# Type_Specific.net
KiCad netlist of a schematic drawn in Altium Designer
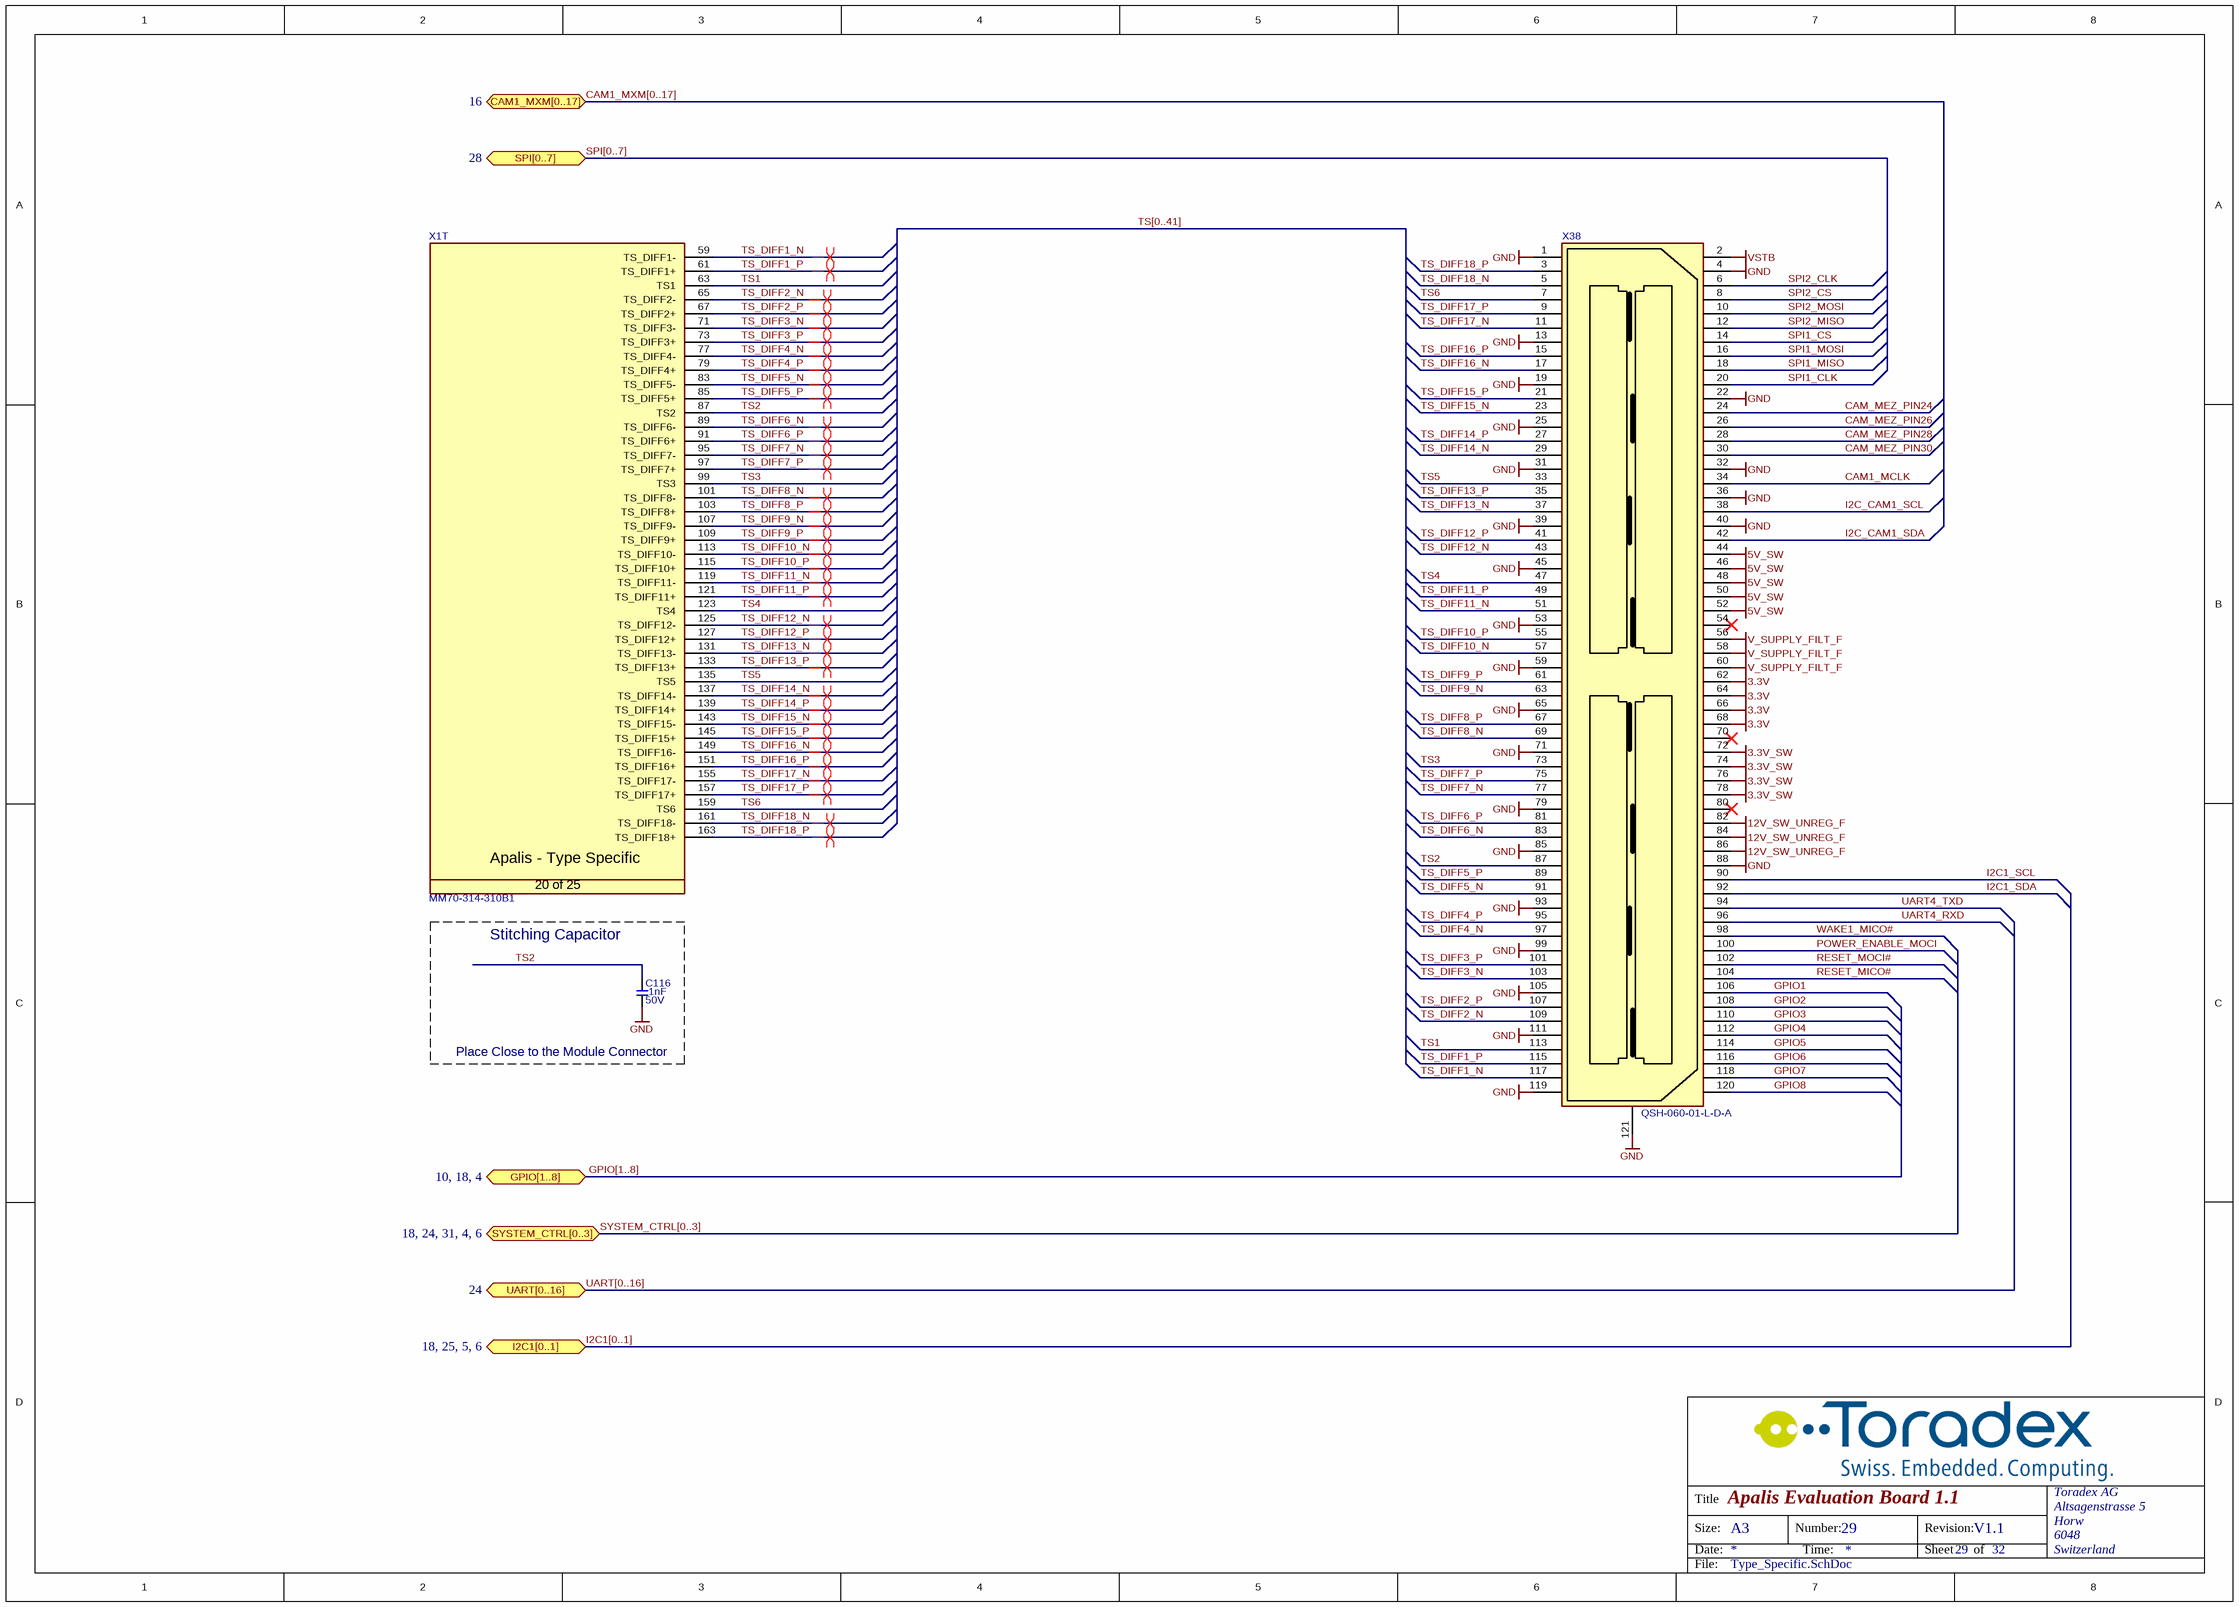
[diagram p0: Type_Specific.SchDoc]

(export (version "E")
  (design (tool "Eeschema 10.0.6"))
  (components
    (comp (ref "C116")
      (value "1nF")
      (footprint "CAPC1005X60N")
      (description "Capacitor Ceramic X7R 1nF 50V 10% 0402")
      (fields (field (name "TOLERANCE") "10%") (field (name "RATING") "50V"))
      (libsource (lib "Apalis Evaluation Board") (part "C-X7R-1nF-50V-10%-0402"))
    )
    (comp (ref "X1")
      (value "CON-JAE-MM70-314-310B1-314-0.5mm")
      (footprint "T_JAE_MM70-314-310B1")
      (description "MXM3 Connector")
      (fields (field (name "MANUFACTURER PART NO.") "MM70-314-310B1"))
      (libsource (lib "Apalis Evaluation Board") (part "CON-JAE-MM70-314-310B1-314-0.5mm"))
    )
    (comp (ref "X38")
      (value "QSH-060-01-L-D-A")
      (footprint "T_Samtech_QSH-060-01-L-D-A")
      (description "High Speed Ground Plane Socket")
      (fields (field (name "MANUFACTURER PART NO.") "QSH-060-01-L-D-A"))
      (libsource (lib "Apalis Evaluation Board") (part "CON-Samtec-QSH-060-01-L-D-A"))
    )
  )
  (nets
    (net (code "86") (name "/CAM1_MCLK") (class "Default")
      (node (ref "X38") (pin "34") (pinfunction "34_34") (pintype "passive"))
    )
    (net (code "88") (name "/CAM_MEZ_PIN24") (class "Default")
      (node (ref "X38") (pin "24") (pinfunction "24_24") (pintype "passive"))
    )
    (net (code "89") (name "/CAM_MEZ_PIN26") (class "Default")
      (node (ref "X38") (pin "26") (pinfunction "26_26") (pintype "passive"))
    )
    (net (code "90") (name "/CAM_MEZ_PIN28") (class "Default")
      (node (ref "X38") (pin "28") (pinfunction "28_28") (pintype "passive"))
    )
    (net (code "91") (name "/CAM_MEZ_PIN30") (class "Default")
      (node (ref "X38") (pin "30") (pinfunction "30_30") (pintype "passive"))
    )
    (net (code "92") (name "/GPIO1") (class "Default")
      (node (ref "X38") (pin "106") (pinfunction "106_106") (pintype "passive"))
    )
    (net (code "93") (name "/GPIO2") (class "Default")
      (node (ref "X38") (pin "108") (pinfunction "108_108") (pintype "passive"))
    )
    (net (code "94") (name "/GPIO3") (class "Default")
      (node (ref "X38") (pin "110") (pinfunction "110_110") (pintype "passive"))
    )
    (net (code "95") (name "/GPIO4") (class "Default")
      (node (ref "X38") (pin "112") (pinfunction "112_112") (pintype "passive"))
    )
    (net (code "96") (name "/GPIO5") (class "Default")
      (node (ref "X38") (pin "114") (pinfunction "114_114") (pintype "passive"))
    )
    (net (code "97") (name "/GPIO6") (class "Default")
      (node (ref "X38") (pin "116") (pinfunction "116_116") (pintype "passive"))
    )
    (net (code "98") (name "/GPIO7") (class "Default")
      (node (ref "X38") (pin "118") (pinfunction "118_118") (pintype "passive"))
    )
    (net (code "99") (name "/GPIO8") (class "Default")
      (node (ref "X38") (pin "120") (pinfunction "120_120") (pintype "passive"))
    )
    (net (code "102") (name "/I2C1_SCL") (class "Default")
      (node (ref "X38") (pin "90") (pinfunction "90_90") (pintype "passive"))
    )
    (net (code "103") (name "/I2C1_SDA") (class "Default")
      (node (ref "X38") (pin "92") (pinfunction "92_92") (pintype "passive"))
    )
    (net (code "104") (name "/I2C_CAM1_SCL") (class "Default")
      (node (ref "X38") (pin "38") (pinfunction "38_38") (pintype "passive"))
    )
    (net (code "105") (name "/I2C_CAM1_SDA") (class "Default")
      (node (ref "X38") (pin "42") (pinfunction "42_42") (pintype "passive"))
    )
    (net (code "106") (name "/POWER_ENABLE_MOCI") (class "Default")
      (node (ref "X38") (pin "100") (pinfunction "100_100") (pintype "passive"))
    )
    (net (code "107") (name "/RESET_MICO#") (class "Default")
      (node (ref "X38") (pin "104") (pinfunction "104_104") (pintype "passive"))
    )
    (net (code "108") (name "/RESET_MOCI#") (class "Default")
      (node (ref "X38") (pin "102") (pinfunction "102_102") (pintype "passive"))
    )
    (net (code "109") (name "/SPI1_CLK") (class "Default")
      (node (ref "X38") (pin "20") (pinfunction "20_20") (pintype "passive"))
    )
    (net (code "110") (name "/SPI1_CS") (class "Default")
      (node (ref "X38") (pin "14") (pinfunction "14_14") (pintype "passive"))
    )
    (net (code "111") (name "/SPI1_MISO") (class "Default")
      (node (ref "X38") (pin "18") (pinfunction "18_18") (pintype "passive"))
    )
    (net (code "112") (name "/SPI1_MOSI") (class "Default")
      (node (ref "X38") (pin "16") (pinfunction "16_16") (pintype "passive"))
    )
    (net (code "113") (name "/SPI2_CLK") (class "Default")
      (node (ref "X38") (pin "6") (pinfunction "6_6") (pintype "passive"))
    )
    (net (code "114") (name "/SPI2_CS") (class "Default")
      (node (ref "X38") (pin "8") (pinfunction "8_8") (pintype "passive"))
    )
    (net (code "115") (name "/SPI2_MISO") (class "Default")
      (node (ref "X38") (pin "12") (pinfunction "12_12") (pintype "passive"))
    )
    (net (code "116") (name "/SPI2_MOSI") (class "Default")
      (node (ref "X38") (pin "10") (pinfunction "10_10") (pintype "passive"))
    )
    (net (code "119") (name "/TS1") (class "Default")
      (node (ref "X1") (pin "63") (pinfunction "TS1_63") (pintype "passive"))
      (node (ref "X38") (pin "113") (pinfunction "113_113") (pintype "passive"))
    )
    (net (code "120") (name "/TS2") (class "Default")
      (node (ref "C116") (pin "2") (pinfunction "2_2") (pintype "passive"))
      (node (ref "X1") (pin "87") (pinfunction "TS2_87") (pintype "passive"))
      (node (ref "X38") (pin "87") (pinfunction "87_87") (pintype "passive"))
    )
    (net (code "121") (name "/TS3") (class "Default")
      (node (ref "X1") (pin "99") (pinfunction "TS3_99") (pintype "passive"))
      (node (ref "X38") (pin "73") (pinfunction "73_73") (pintype "passive"))
    )
    (net (code "122") (name "/TS4") (class "Default")
      (node (ref "X1") (pin "123") (pinfunction "TS4_123") (pintype "passive"))
      (node (ref "X38") (pin "47") (pinfunction "47_47") (pintype "passive"))
    )
    (net (code "123") (name "/TS5") (class "Default")
      (node (ref "X1") (pin "135") (pinfunction "TS5_135") (pintype "passive"))
      (node (ref "X38") (pin "33") (pinfunction "33_33") (pintype "passive"))
    )
    (net (code "124") (name "/TS6") (class "Default")
      (node (ref "X1") (pin "159") (pinfunction "TS6_159") (pintype "passive"))
      (node (ref "X38") (pin "7") (pinfunction "7_7") (pintype "passive"))
    )
    (net (code "126") (name "/TS_DIFF1_N") (class "Default")
      (node (ref "X1") (pin "59") (pinfunction "TS_DIFF1-_59") (pintype "passive"))
      (node (ref "X38") (pin "117") (pinfunction "117_117") (pintype "passive"))
    )
    (net (code "127") (name "/TS_DIFF1_P") (class "Default")
      (node (ref "X1") (pin "61") (pinfunction "TS_DIFF1+_61") (pintype "passive"))
      (node (ref "X38") (pin "115") (pinfunction "115_115") (pintype "passive"))
    )
    (net (code "128") (name "/TS_DIFF2_N") (class "Default")
      (node (ref "X1") (pin "65") (pinfunction "TS_DIFF2-_65") (pintype "passive"))
      (node (ref "X38") (pin "109") (pinfunction "109_109") (pintype "passive"))
    )
    (net (code "129") (name "/TS_DIFF2_P") (class "Default")
      (node (ref "X1") (pin "67") (pinfunction "TS_DIFF2+_67") (pintype "passive"))
      (node (ref "X38") (pin "107") (pinfunction "107_107") (pintype "passive"))
    )
    (net (code "130") (name "/TS_DIFF3_N") (class "Default")
      (node (ref "X1") (pin "71") (pinfunction "TS_DIFF3-_71") (pintype "passive"))
      (node (ref "X38") (pin "103") (pinfunction "103_103") (pintype "passive"))
    )
    (net (code "131") (name "/TS_DIFF3_P") (class "Default")
      (node (ref "X1") (pin "73") (pinfunction "TS_DIFF3+_73") (pintype "passive"))
      (node (ref "X38") (pin "101") (pinfunction "101_101") (pintype "passive"))
    )
    (net (code "132") (name "/TS_DIFF4_N") (class "Default")
      (node (ref "X1") (pin "77") (pinfunction "TS_DIFF4-_77") (pintype "passive"))
      (node (ref "X38") (pin "97") (pinfunction "97_97") (pintype "passive"))
    )
    (net (code "133") (name "/TS_DIFF4_P") (class "Default")
      (node (ref "X1") (pin "79") (pinfunction "TS_DIFF4+_79") (pintype "passive"))
      (node (ref "X38") (pin "95") (pinfunction "95_95") (pintype "passive"))
    )
    (net (code "134") (name "/TS_DIFF5_N") (class "Default")
      (node (ref "X1") (pin "83") (pinfunction "TS_DIFF5-_83") (pintype "passive"))
      (node (ref "X38") (pin "91") (pinfunction "91_91") (pintype "passive"))
    )
    (net (code "135") (name "/TS_DIFF5_P") (class "Default")
      (node (ref "X1") (pin "85") (pinfunction "TS_DIFF5+_85") (pintype "passive"))
      (node (ref "X38") (pin "89") (pinfunction "89_89") (pintype "passive"))
    )
    (net (code "136") (name "/TS_DIFF6_N") (class "Default")
      (node (ref "X1") (pin "89") (pinfunction "TS_DIFF6-_89") (pintype "passive"))
      (node (ref "X38") (pin "83") (pinfunction "83_83") (pintype "passive"))
    )
    (net (code "137") (name "/TS_DIFF6_P") (class "Default")
      (node (ref "X1") (pin "91") (pinfunction "TS_DIFF6+_91") (pintype "passive"))
      (node (ref "X38") (pin "81") (pinfunction "81_81") (pintype "passive"))
    )
    (net (code "138") (name "/TS_DIFF7_N") (class "Default")
      (node (ref "X1") (pin "95") (pinfunction "TS_DIFF7-_95") (pintype "passive"))
      (node (ref "X38") (pin "77") (pinfunction "77_77") (pintype "passive"))
    )
    (net (code "139") (name "/TS_DIFF7_P") (class "Default")
      (node (ref "X1") (pin "97") (pinfunction "TS_DIFF7+_97") (pintype "passive"))
      (node (ref "X38") (pin "75") (pinfunction "75_75") (pintype "passive"))
    )
    (net (code "140") (name "/TS_DIFF8_N") (class "Default")
      (node (ref "X1") (pin "101") (pinfunction "TS_DIFF8-_101") (pintype "passive"))
      (node (ref "X38") (pin "69") (pinfunction "69_69") (pintype "passive"))
    )
    (net (code "141") (name "/TS_DIFF8_P") (class "Default")
      (node (ref "X1") (pin "103") (pinfunction "TS_DIFF8+_103") (pintype "passive"))
      (node (ref "X38") (pin "67") (pinfunction "67_67") (pintype "passive"))
    )
    (net (code "142") (name "/TS_DIFF9_N") (class "Default")
      (node (ref "X1") (pin "107") (pinfunction "TS_DIFF9-_107") (pintype "passive"))
      (node (ref "X38") (pin "63") (pinfunction "63_63") (pintype "passive"))
    )
    (net (code "143") (name "/TS_DIFF9_P") (class "Default")
      (node (ref "X1") (pin "109") (pinfunction "TS_DIFF9+_109") (pintype "passive"))
      (node (ref "X38") (pin "61") (pinfunction "61_61") (pintype "passive"))
    )
    (net (code "144") (name "/TS_DIFF10_N") (class "Default")
      (node (ref "X1") (pin "113") (pinfunction "TS_DIFF10-_113") (pintype "passive"))
      (node (ref "X38") (pin "57") (pinfunction "57_57") (pintype "passive"))
    )
    (net (code "145") (name "/TS_DIFF10_P") (class "Default")
      (node (ref "X1") (pin "115") (pinfunction "TS_DIFF10+_115") (pintype "passive"))
      (node (ref "X38") (pin "55") (pinfunction "55_55") (pintype "passive"))
    )
    (net (code "146") (name "/TS_DIFF11_N") (class "Default")
      (node (ref "X1") (pin "119") (pinfunction "TS_DIFF11-_119") (pintype "passive"))
      (node (ref "X38") (pin "51") (pinfunction "51_51") (pintype "passive"))
    )
    (net (code "147") (name "/TS_DIFF11_P") (class "Default")
      (node (ref "X1") (pin "121") (pinfunction "TS_DIFF11+_121") (pintype "passive"))
      (node (ref "X38") (pin "49") (pinfunction "49_49") (pintype "passive"))
    )
    (net (code "148") (name "/TS_DIFF12_N") (class "Default")
      (node (ref "X1") (pin "125") (pinfunction "TS_DIFF12-_125") (pintype "passive"))
      (node (ref "X38") (pin "43") (pinfunction "43_43") (pintype "passive"))
    )
    (net (code "149") (name "/TS_DIFF12_P") (class "Default")
      (node (ref "X1") (pin "127") (pinfunction "TS_DIFF12+_127") (pintype "passive"))
      (node (ref "X38") (pin "41") (pinfunction "41_41") (pintype "passive"))
    )
    (net (code "150") (name "/TS_DIFF13_N") (class "Default")
      (node (ref "X1") (pin "131") (pinfunction "TS_DIFF13-_131") (pintype "passive"))
      (node (ref "X38") (pin "37") (pinfunction "37_37") (pintype "passive"))
    )
    (net (code "151") (name "/TS_DIFF13_P") (class "Default")
      (node (ref "X1") (pin "133") (pinfunction "TS_DIFF13+_133") (pintype "passive"))
      (node (ref "X38") (pin "35") (pinfunction "35_35") (pintype "passive"))
    )
    (net (code "152") (name "/TS_DIFF14_N") (class "Default")
      (node (ref "X1") (pin "137") (pinfunction "TS_DIFF14-_137") (pintype "passive"))
      (node (ref "X38") (pin "29") (pinfunction "29_29") (pintype "passive"))
    )
    (net (code "153") (name "/TS_DIFF14_P") (class "Default")
      (node (ref "X1") (pin "139") (pinfunction "TS_DIFF14+_139") (pintype "passive"))
      (node (ref "X38") (pin "27") (pinfunction "27_27") (pintype "passive"))
    )
    (net (code "154") (name "/TS_DIFF15_N") (class "Default")
      (node (ref "X1") (pin "143") (pinfunction "TS_DIFF15-_143") (pintype "passive"))
      (node (ref "X38") (pin "23") (pinfunction "23_23") (pintype "passive"))
    )
    (net (code "155") (name "/TS_DIFF15_P") (class "Default")
      (node (ref "X1") (pin "145") (pinfunction "TS_DIFF15+_145") (pintype "passive"))
      (node (ref "X38") (pin "21") (pinfunction "21_21") (pintype "passive"))
    )
    (net (code "156") (name "/TS_DIFF16_N") (class "Default")
      (node (ref "X1") (pin "149") (pinfunction "TS_DIFF16-_149") (pintype "passive"))
      (node (ref "X38") (pin "17") (pinfunction "17_17") (pintype "passive"))
    )
    (net (code "157") (name "/TS_DIFF16_P") (class "Default")
      (node (ref "X1") (pin "151") (pinfunction "TS_DIFF16+_151") (pintype "passive"))
      (node (ref "X38") (pin "15") (pinfunction "15_15") (pintype "passive"))
    )
    (net (code "158") (name "/TS_DIFF17_N") (class "Default")
      (node (ref "X1") (pin "155") (pinfunction "TS_DIFF17-_155") (pintype "passive"))
      (node (ref "X38") (pin "11") (pinfunction "11_11") (pintype "passive"))
    )
    (net (code "159") (name "/TS_DIFF17_P") (class "Default")
      (node (ref "X1") (pin "157") (pinfunction "TS_DIFF17+_157") (pintype "passive"))
      (node (ref "X38") (pin "9") (pinfunction "9_9") (pintype "passive"))
    )
    (net (code "160") (name "/TS_DIFF18_N") (class "Default")
      (node (ref "X1") (pin "161") (pinfunction "TS_DIFF18-_161") (pintype "passive"))
      (node (ref "X38") (pin "5") (pinfunction "5_5") (pintype "passive"))
    )
    (net (code "161") (name "/TS_DIFF18_P") (class "Default")
      (node (ref "X1") (pin "163") (pinfunction "TS_DIFF18+_163") (pintype "passive"))
      (node (ref "X38") (pin "3") (pinfunction "3_3") (pintype "passive"))
    )
    (net (code "162") (name "/UART4_RXD") (class "Default")
      (node (ref "X38") (pin "96") (pinfunction "96_96") (pintype "passive"))
    )
    (net (code "163") (name "/UART4_TXD") (class "Default")
      (node (ref "X38") (pin "94") (pinfunction "94_94") (pintype "passive"))
    )
    (net (code "165") (name "/WAKE1_MICO#") (class "Default")
      (node (ref "X38") (pin "98") (pinfunction "98_98") (pintype "passive"))
    )
    (net (code "166") (name "3.3V") (class "Default")
      (node (ref "X38") (pin "62") (pinfunction "62_62") (pintype "passive"))
      (node (ref "X38") (pin "64") (pinfunction "64_64") (pintype "passive"))
      (node (ref "X38") (pin "66") (pinfunction "66_66") (pintype "passive"))
      (node (ref "X38") (pin "68") (pinfunction "68_68") (pintype "passive"))
    )
    (net (code "167") (name "3.3V_SW") (class "Default")
      (node (ref "X38") (pin "72") (pinfunction "72_72") (pintype "passive"))
      (node (ref "X38") (pin "74") (pinfunction "74_74") (pintype "passive"))
      (node (ref "X38") (pin "76") (pinfunction "76_76") (pintype "passive"))
      (node (ref "X38") (pin "78") (pinfunction "78_78") (pintype "passive"))
    )
    (net (code "168") (name "5V_SW") (class "Default")
      (node (ref "X38") (pin "44") (pinfunction "44_44") (pintype "passive"))
      (node (ref "X38") (pin "46") (pinfunction "46_46") (pintype "passive"))
      (node (ref "X38") (pin "48") (pinfunction "48_48") (pintype "passive"))
      (node (ref "X38") (pin "50") (pinfunction "50_50") (pintype "passive"))
      (node (ref "X38") (pin "52") (pinfunction "52_52") (pintype "passive"))
    )
    (net (code "169") (name "12V_SW_UNREG_F") (class "Default")
      (node (ref "X38") (pin "82") (pinfunction "82_82") (pintype "passive"))
      (node (ref "X38") (pin "84") (pinfunction "84_84") (pintype "passive"))
      (node (ref "X38") (pin "86") (pinfunction "86_86") (pintype "passive"))
    )
    (net (code "170") (name "GND") (class "Default")
      (node (ref "C116") (pin "1") (pinfunction "1_1") (pintype "passive"))
      (node (ref "X38") (pin "1") (pinfunction "1_1") (pintype "passive"))
      (node (ref "X38") (pin "105") (pinfunction "105_105") (pintype "passive"))
      (node (ref "X38") (pin "111") (pinfunction "111_111") (pintype "passive"))
      (node (ref "X38") (pin "119") (pinfunction "119_119") (pintype "passive"))
      (node (ref "X38") (pin "121") (pinfunction "121_121") (pintype "passive"))
      (node (ref "X38") (pin "13") (pinfunction "13_13") (pintype "passive"))
      (node (ref "X38") (pin "19") (pinfunction "19_19") (pintype "passive"))
      (node (ref "X38") (pin "22") (pinfunction "22_22") (pintype "passive"))
      (node (ref "X38") (pin "25") (pinfunction "25_25") (pintype "passive"))
      (node (ref "X38") (pin "31") (pinfunction "31_31") (pintype "passive"))
      (node (ref "X38") (pin "32") (pinfunction "32_32") (pintype "passive"))
      (node (ref "X38") (pin "36") (pinfunction "36_36") (pintype "passive"))
      (node (ref "X38") (pin "39") (pinfunction "39_39") (pintype "passive"))
      (node (ref "X38") (pin "4") (pinfunction "4_4") (pintype "passive"))
      (node (ref "X38") (pin "40") (pinfunction "40_40") (pintype "passive"))
      (node (ref "X38") (pin "45") (pinfunction "45_45") (pintype "passive"))
      (node (ref "X38") (pin "53") (pinfunction "53_53") (pintype "passive"))
      (node (ref "X38") (pin "59") (pinfunction "59_59") (pintype "passive"))
      (node (ref "X38") (pin "65") (pinfunction "65_65") (pintype "passive"))
      (node (ref "X38") (pin "71") (pinfunction "71_71") (pintype "passive"))
      (node (ref "X38") (pin "79") (pinfunction "79_79") (pintype "passive"))
      (node (ref "X38") (pin "85") (pinfunction "85_85") (pintype "passive"))
      (node (ref "X38") (pin "88") (pinfunction "88_88") (pintype "passive"))
      (node (ref "X38") (pin "93") (pinfunction "93_93") (pintype "passive"))
      (node (ref "X38") (pin "99") (pinfunction "99_99") (pintype "passive"))
    )
    (net (code "171") (name "VSTB") (class "Default")
      (node (ref "X38") (pin "2") (pinfunction "2_2") (pintype "passive"))
    )
    (net (code "172") (name "V_SUPPLY_FILT_F") (class "Default")
      (node (ref "X38") (pin "56") (pinfunction "56_56") (pintype "passive"))
      (node (ref "X38") (pin "58") (pinfunction "58_58") (pintype "passive"))
      (node (ref "X38") (pin "60") (pinfunction "60_60") (pintype "passive"))
    )
    (net (code "173") (name "unconnected-(X38-Pad54)") (class "Default")
      (node (ref "X38") (pin "54") (pinfunction "54_54") (pintype "passive+no_connect"))
    )
    (net (code "174") (name "unconnected-(X38-Pad70)") (class "Default")
      (node (ref "X38") (pin "70") (pinfunction "70_70") (pintype "passive+no_connect"))
    )
    (net (code "175") (name "unconnected-(X38-Pad80)") (class "Default")
      (node (ref "X38") (pin "80") (pinfunction "80_80") (pintype "passive+no_connect"))
    )
  )
)
